# vesc.net
KiCad netlist of a schematic drawn in Altium Designer
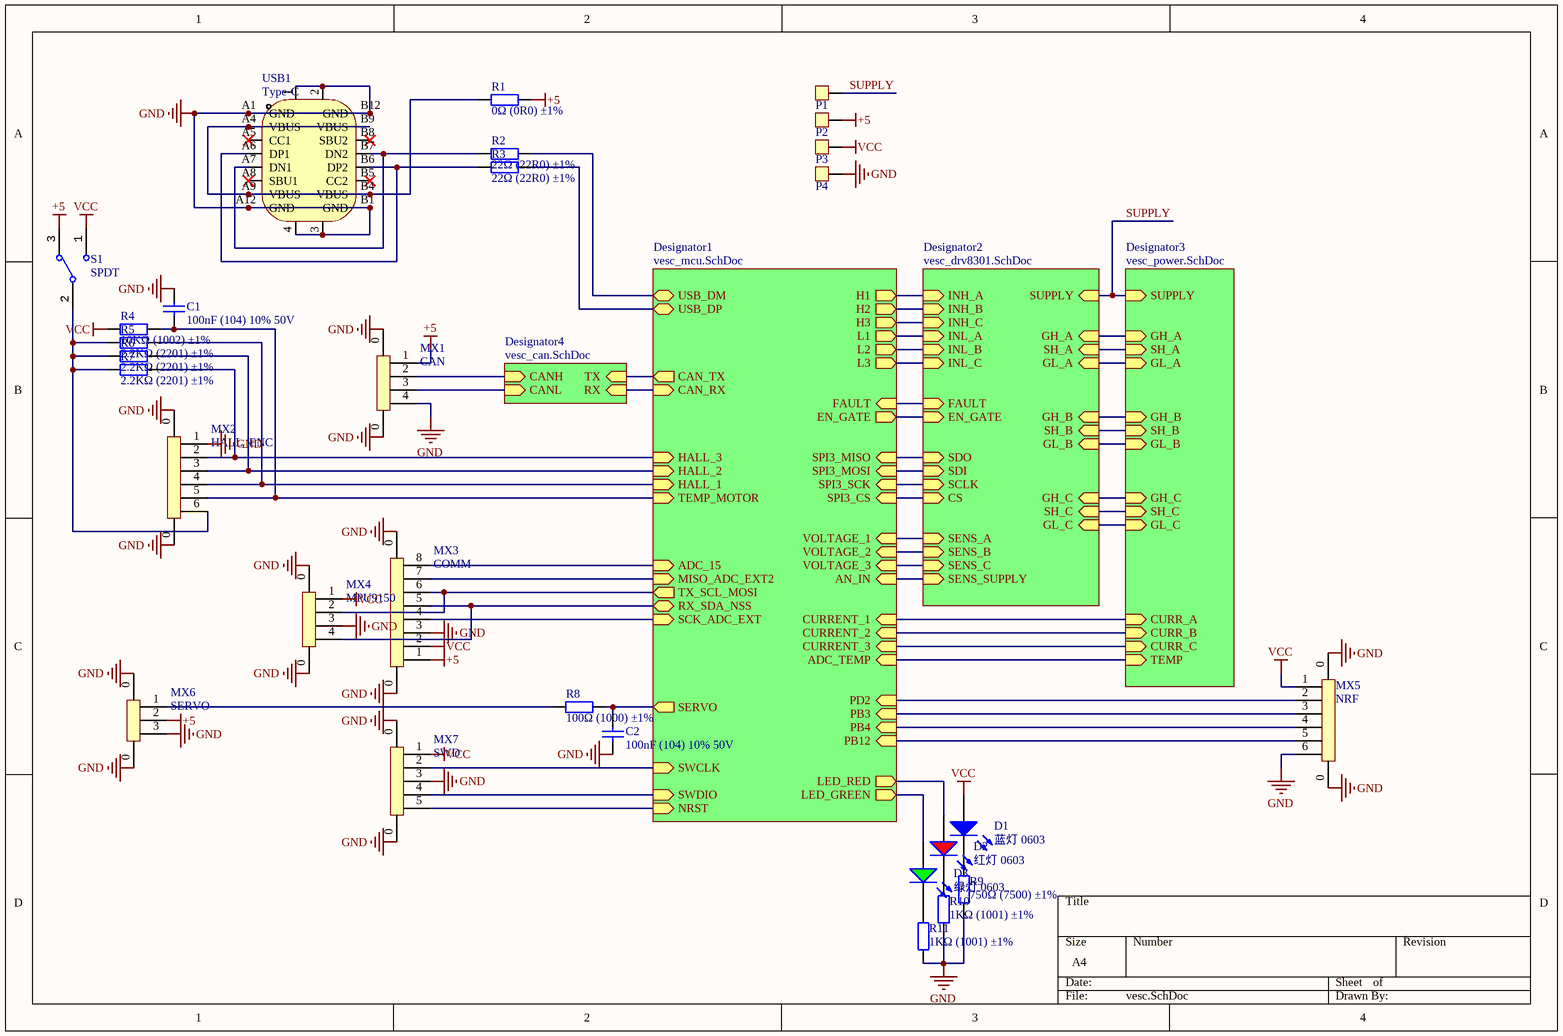
[diagram p0: vesc.SchDoc]

(export (version "E")
  (design (tool "Eeschema 10.0.6"))
  (components
    (comp (ref "C1")
      (value "100nF (104) 10% 50V")
      (footprint "0603_C")
      (description "贴片电容")
      (libsource (lib "Miscellaneous Devices LC") (part "0603 100nF (104) 10% 50V"))
    )
    (comp (ref "C2")
      (value "100nF (104) 10% 50V")
      (footprint "0603_C")
      (description "贴片电容")
      (libsource (lib "Miscellaneous Devices LC") (part "0603 100nF (104) 10% 50V"))
    )
    (comp (ref "D1")
      (value "蓝灯 0603")
      (footprint "0603_LED_S1")
      (description "发光二极管")
      (libsource (lib "Miscellaneous Devices LC") (part "0603 蓝灯"))
    )
    (comp (ref "D2")
      (value "红灯 0603")
      (footprint "0603_LED_S1")
      (description "发光二极管")
      (libsource (lib "Miscellaneous Devices LC") (part "0603 红灯"))
    )
    (comp (ref "D3")
      (value "绿灯 0603")
      (footprint "0603_LED_S1")
      (description "发光二极管")
      (libsource (lib "Miscellaneous Devices LC") (part "0603 绿灯"))
    )
    (comp (ref "MX1") (value "CAN") (footprint "MX 1.25-WS-4P") (libsource (lib "vesc") (part "MX_WS_4P")))
    (comp (ref "MX2") (value "HALL_ENC") (footprint "MX 1.25-WS-6P") (libsource (lib "") (part "MX_WS_6P_1")))
    (comp (ref "MX3") (value "COMM") (footprint "MX 1.25-WS-8P") (libsource (lib "vesc") (part "MX_WS_8P")))
    (comp (ref "MX4")
      (value "MPU9150")
      (footprint "MX 1.25-WS-4P")
      (libsource (lib "vesc") (part "MX_WS_4P"))
    )
    (comp (ref "MX5") (value "NRF") (footprint "MX 1.25-WS-6P") (libsource (lib "vesc") (part "MX_WS_6P")))
    (comp (ref "MX6") (value "SERVO") (footprint "MX 1.25-WS-3P") (libsource (lib "vesc") (part "MX_WS_3P")))
    (comp (ref "MX7") (value "SWD") (footprint "MX 1.25-WS-5P") (libsource (lib "vesc") (part "MX_WS_5P")))
    (comp (ref "P1")
      (value "PAD")
      (footprint "PAD")
      (fields (field (name "MANUFACTURER") "AMASS(艾迈斯)") (field (name "MANUFACTURER PART") "XT30U-M"))
      (libsource (lib "vesc") (part "PAD"))
    )
    (comp (ref "P2")
      (value "PAD")
      (footprint "PAD")
      (fields (field (name "MANUFACTURER") "AMASS(艾迈斯)") (field (name "MANUFACTURER PART") "XT30U-M"))
      (libsource (lib "vesc") (part "PAD"))
    )
    (comp (ref "P3")
      (value "PAD")
      (footprint "PAD")
      (fields (field (name "MANUFACTURER") "AMASS(艾迈斯)") (field (name "MANUFACTURER PART") "XT30U-M"))
      (libsource (lib "vesc") (part "PAD"))
    )
    (comp (ref "P4")
      (value "PAD")
      (footprint "PAD")
      (fields (field (name "MANUFACTURER") "AMASS(艾迈斯)") (field (name "MANUFACTURER PART") "XT30U-M"))
      (libsource (lib "vesc") (part "PAD"))
    )
    (comp (ref "R1")
      (value "0Ω (0R0) ±1%")
      (footprint "0603_R")
      (description "贴片电阻")
      (libsource (lib "Miscellaneous Devices LC") (part "0603 0Ω (0R0) 1%"))
    )
    (comp (ref "R2")
      (value "22Ω (22R0) ±1%")
      (footprint "0603_R")
      (description "贴片电阻")
      (libsource (lib "Miscellaneous Devices LC") (part "0603 22Ω (22R0) 1%"))
    )
    (comp (ref "R3")
      (value "22Ω (22R0) ±1%")
      (footprint "0603_R")
      (description "贴片电阻")
      (libsource (lib "Miscellaneous Devices LC") (part "0603 22Ω (22R0) 1%"))
    )
    (comp (ref "R4")
      (value "10KΩ (1002) ±1%")
      (footprint "0603_R")
      (description "贴片电阻")
      (libsource (lib "Miscellaneous Devices LC") (part "0603 10KΩ (1002) 1%"))
    )
    (comp (ref "R5")
      (value "2.2KΩ (2201) ±1%")
      (footprint "0603_R")
      (description "贴片电阻")
      (libsource (lib "Miscellaneous Devices LC") (part "0603 2.2KΩ (2201) 1%"))
    )
    (comp (ref "R6")
      (value "2.2KΩ (2201) ±1%")
      (footprint "0603_R")
      (description "贴片电阻")
      (libsource (lib "Miscellaneous Devices LC") (part "0603 2.2KΩ (2201) 1%"))
    )
    (comp (ref "R7")
      (value "2.2KΩ (2201) ±1%")
      (footprint "0603_R")
      (description "贴片电阻")
      (libsource (lib "Miscellaneous Devices LC") (part "0603 2.2KΩ (2201) 1%"))
    )
    (comp (ref "R8")
      (value "100Ω (1000) ±1%")
      (footprint "0603_R")
      (description "贴片电阻")
      (libsource (lib "Miscellaneous Devices LC") (part "0603 100Ω (1000) 1%"))
    )
    (comp (ref "R9")
      (value "750Ω (7500) ±1%")
      (footprint "0603_R")
      (description "贴片电阻")
      (libsource (lib "Miscellaneous Devices LC") (part "0603 750Ω (7500) 1%"))
    )
    (comp (ref "R10")
      (value "1KΩ (1001) ±1%")
      (footprint "0603_R")
      (description "贴片电阻")
      (libsource (lib "Miscellaneous Devices LC") (part "0603 1KΩ (1001) 1%"))
    )
    (comp (ref "R11")
      (value "1KΩ (1001) ±1%")
      (footprint "0603_R")
      (description "贴片电阻")
      (libsource (lib "Miscellaneous Devices LC") (part "0603 1KΩ (1001) 1%"))
    )
    (comp (ref "S1")
      (value "SPDT")
      (footprint "PCB_Switch:SwitchSPDT_4.3X8.6_D90")
      (description "Switch")
      (libsource (lib "SCH_Switch") (part "SwitchSPDT_90DIP_4.3x8.6"))
    )
    (comp (ref "USB1")
      (value "Type-C")
      (footprint "TYPE-C_16P")
      (description "USB-Type-C_16P")
      (libsource (lib "Connector") (part "USB-Type-C"))
    )
  )
  (nets
    (net (code "1") (name "+5") (class "Default")
      (node (ref "MX1") (pin "1") (pintype "passive"))
      (node (ref "MX3") (pin "1") (pintype "passive"))
      (node (ref "MX6") (pin "2") (pintype "passive"))
      (node (ref "P2") (pin "1") (pintype "passive"))
      (node (ref "R1") (pin "2") (pinfunction "2_2") (pintype "passive"))
      (node (ref "S1") (pin "3") (pinfunction "3_3") (pintype "passive"))
    )
    (net (code "2") (name "/ADC_15") (class "Default")
      (node (ref "MX3") (pin "8") (pinfunction "8_8") (pintype "passive"))
    )
    (net (code "5") (name "/CANH") (class "Default") (node (ref "MX1") (pin "2") (pintype "passive")))
    (net (code "6") (name "/CANL") (class "Default") (node (ref "MX1") (pin "3") (pintype "passive")))
    (net (code "24") (name "/HALL_1") (class "Default")
      (node (ref "MX2") (pin "4") (pintype "passive"))
      (node (ref "R5") (pin "2") (pinfunction "2_2") (pintype "passive"))
    )
    (net (code "25") (name "/HALL_2") (class "Default")
      (node (ref "MX2") (pin "3") (pintype "passive"))
      (node (ref "R6") (pin "2") (pinfunction "2_2") (pintype "passive"))
    )
    (net (code "26") (name "/HALL_3") (class "Default")
      (node (ref "MX2") (pin "2") (pintype "passive"))
      (node (ref "R7") (pin "2") (pinfunction "2_2") (pintype "passive"))
    )
    (net (code "30") (name "/LED_GREEN") (class "Default")
      (node (ref "D3") (pin "A") (pinfunction "A_A") (pintype "passive"))
    )
    (net (code "31") (name "/LED_RED") (class "Default")
      (node (ref "D2") (pin "A") (pinfunction "A_A") (pintype "passive"))
    )
    (net (code "32") (name "/MISO_ADC_EXT2") (class "Default")
      (node (ref "MX3") (pin "7") (pinfunction "7_7") (pintype "passive"))
    )
    (net (code "33") (name "/NRST") (class "Default")
      (node (ref "MX7") (pin "5") (pinfunction "5_5") (pintype "passive"))
    )
    (net (code "34") (name "/PB3") (class "Default") (node (ref "MX5") (pin "3") (pintype "passive")))
    (net (code "35") (name "/PB4") (class "Default") (node (ref "MX5") (pin "4") (pintype "passive")))
    (net (code "36") (name "/PB12") (class "Default")
      (node (ref "MX5") (pin "5") (pinfunction "5_5") (pintype "passive"))
    )
    (net (code "37") (name "/PD2") (class "Default") (node (ref "MX5") (pin "2") (pintype "passive")))
    (net (code "38") (name "/RX_SDA_NSS") (class "Default")
      (node (ref "MX3") (pin "5") (pinfunction "5_5") (pintype "passive"))
      (node (ref "MX4") (pin "4") (pintype "passive"))
    )
    (net (code "39") (name "/SCK_ADC_EXT") (class "Default") (node (ref "MX3") (pin "4") (pintype "passive")))
    (net (code "46") (name "/SERVO") (class "Default")
      (node (ref "C2") (pin "2") (pinfunction "2_2") (pintype "passive"))
      (node (ref "R8") (pin "2") (pinfunction "2_2") (pintype "passive"))
    )
    (net (code "50") (name "/SUPPLY") (class "Default") (node (ref "P1") (pin "1") (pintype "passive")))
    (net (code "51") (name "/SWCLK") (class "Default") (node (ref "MX7") (pin "2") (pintype "passive")))
    (net (code "52") (name "/SWDIO") (class "Default") (node (ref "MX7") (pin "4") (pintype "passive")))
    (net (code "53") (name "/TEMP_MOTOR") (class "Default")
      (node (ref "C1") (pin "1") (pinfunction "1_1") (pintype "passive"))
      (node (ref "MX2") (pin "5") (pinfunction "5_5") (pintype "passive"))
      (node (ref "R4") (pin "2") (pinfunction "2_2") (pintype "passive"))
    )
    (net (code "54") (name "/TX_SCL_MOSI") (class "Default")
      (node (ref "MX3") (pin "6") (pinfunction "6_6") (pintype "passive"))
      (node (ref "MX4") (pin "2") (pintype "passive"))
    )
    (net (code "55") (name "/USB_DM") (class "Default")
      (node (ref "R2") (pin "2") (pinfunction "2_2") (pintype "passive"))
    )
    (net (code "56") (name "/USB_DP") (class "Default")
      (node (ref "R3") (pin "2") (pinfunction "2_2") (pintype "passive"))
    )
    (net (code "57") (name "GND") (class "Default")
      (node (ref "C1") (pin "2") (pinfunction "2_2") (pintype "passive"))
      (node (ref "C2") (pin "1") (pinfunction "1_1") (pintype "passive"))
      (node (ref "MX1") (pin "0") (pintype "power_in"))
      (node (ref "MX1") (pin "4") (pintype "passive"))
      (node (ref "MX2") (pin "0") (pintype "power_in"))
      (node (ref "MX2") (pin "1") (pintype "passive"))
      (node (ref "MX3") (pin "0") (pintype "power_in"))
      (node (ref "MX3") (pin "3") (pintype "passive"))
      (node (ref "MX4") (pin "0") (pintype "power_in"))
      (node (ref "MX4") (pin "3") (pintype "passive"))
      (node (ref "MX5") (pin "0") (pintype "power_in"))
      (node (ref "MX5") (pin "6") (pinfunction "6_6") (pintype "passive"))
      (node (ref "MX6") (pin "0") (pintype "power_in"))
      (node (ref "MX6") (pin "3") (pintype "passive"))
      (node (ref "MX7") (pin "0") (pintype "power_in"))
      (node (ref "MX7") (pin "3") (pintype "passive"))
      (node (ref "P4") (pin "1") (pintype "passive"))
      (node (ref "R10") (pin "1") (pinfunction "1_1") (pintype "passive"))
      (node (ref "R11") (pin "1") (pinfunction "1_1") (pintype "passive"))
      (node (ref "R9") (pin "1") (pinfunction "1_1") (pintype "passive"))
      (node (ref "USB1") (pin "1") (pinfunction "2_1") (pintype "passive"))
      (node (ref "USB1") (pin "2") (pinfunction "2_2") (pintype "passive"))
      (node (ref "USB1") (pin "3") (pinfunction "3_3") (pintype "passive"))
      (node (ref "USB1") (pin "4") (pinfunction "4_4") (pintype "passive"))
      (node (ref "USB1") (pin "A1") (pinfunction "GND_A1") (pintype "passive"))
      (node (ref "USB1") (pin "A12") (pinfunction "GND_A12") (pintype "passive"))
      (node (ref "USB1") (pin "B1") (pinfunction "GND_B1") (pintype "passive"))
      (node (ref "USB1") (pin "B12") (pinfunction "GND_B12") (pintype "passive"))
    )
    (net (code "58") (name "Net-(D1-PadK)") (class "Default")
      (node (ref "D1") (pin "K") (pinfunction "K_K") (pintype "passive"))
      (node (ref "R9") (pin "2") (pinfunction "2_2") (pintype "passive"))
    )
    (net (code "59") (name "Net-(D2-PadK)") (class "Default")
      (node (ref "D2") (pin "K") (pinfunction "K_K") (pintype "passive"))
      (node (ref "R10") (pin "2") (pinfunction "2_2") (pintype "passive"))
    )
    (net (code "60") (name "Net-(D3-PadK)") (class "Default")
      (node (ref "D3") (pin "K") (pinfunction "K_K") (pintype "passive"))
      (node (ref "R11") (pin "2") (pinfunction "2_2") (pintype "passive"))
    )
    (net (code "61") (name "Net-(MX2-Pad6)") (class "Default")
      (node (ref "MX2") (pin "6") (pinfunction "6_6") (pintype "passive"))
      (node (ref "R5") (pin "1") (pinfunction "1_1") (pintype "passive"))
      (node (ref "R6") (pin "1") (pinfunction "1_1") (pintype "passive"))
      (node (ref "R7") (pin "1") (pinfunction "1_1") (pintype "passive"))
      (node (ref "S1") (pin "2") (pinfunction "2_2") (pintype "passive"))
    )
    (net (code "62") (name "Net-(MX6-Pad1)") (class "Default")
      (node (ref "MX6") (pin "1") (pintype "passive"))
      (node (ref "R8") (pin "1") (pinfunction "1_1") (pintype "passive"))
    )
    (net (code "63") (name "Net-(R1-Pad1)") (class "Default")
      (node (ref "R1") (pin "1") (pinfunction "1_1") (pintype "passive"))
      (node (ref "USB1") (pin "A4") (pinfunction "VBUS_A4") (pintype "passive"))
      (node (ref "USB1") (pin "A9") (pinfunction "VBUS_A9") (pintype "passive"))
      (node (ref "USB1") (pin "B4") (pinfunction "VBUS_B4") (pintype "passive"))
      (node (ref "USB1") (pin "B9") (pinfunction "VBUS_B9") (pintype "passive"))
    )
    (net (code "64") (name "Net-(USB1-DN1)") (class "Default")
      (node (ref "R2") (pin "1") (pinfunction "1_1") (pintype "passive"))
      (node (ref "USB1") (pin "A7") (pinfunction "DN1_A7") (pintype "passive"))
      (node (ref "USB1") (pin "B7") (pinfunction "DN2_B7") (pintype "passive"))
    )
    (net (code "65") (name "Net-(USB1-DP1)") (class "Default")
      (node (ref "R3") (pin "1") (pinfunction "1_1") (pintype "passive"))
      (node (ref "USB1") (pin "A6") (pinfunction "DP1_A6") (pintype "passive"))
      (node (ref "USB1") (pin "B6") (pinfunction "DP2_B6") (pintype "passive"))
    )
    (net (code "66") (name "VCC") (class "Default")
      (node (ref "D1") (pin "A") (pinfunction "A_A") (pintype "passive"))
      (node (ref "MX3") (pin "2") (pintype "passive"))
      (node (ref "MX4") (pin "1") (pintype "passive"))
      (node (ref "MX5") (pin "1") (pintype "passive"))
      (node (ref "MX7") (pin "1") (pintype "passive"))
      (node (ref "P3") (pin "1") (pintype "passive"))
      (node (ref "R4") (pin "1") (pinfunction "1_1") (pintype "passive"))
      (node (ref "S1") (pin "1") (pinfunction "1_1") (pintype "passive"))
    )
    (net (code "67") (name "unconnected-(USB1-CC1-PadA5)") (class "Default")
      (node (ref "USB1") (pin "A5") (pinfunction "CC1_A5") (pintype "passive+no_connect"))
    )
    (net (code "68") (name "unconnected-(USB1-CC2-PadB5)") (class "Default")
      (node (ref "USB1") (pin "B5") (pinfunction "CC2_B5") (pintype "passive+no_connect"))
    )
    (net (code "69") (name "unconnected-(USB1-SBU1-PadA8)") (class "Default")
      (node (ref "USB1") (pin "A8") (pinfunction "SBU1_A8") (pintype "passive+no_connect"))
    )
    (net (code "70") (name "unconnected-(USB1-SBU2-PadB8)") (class "Default")
      (node (ref "USB1") (pin "B8") (pinfunction "SBU2_B8") (pintype "passive+no_connect"))
    )
  )
)
